# C.net
KiCad netlist of a schematic drawn in Altium Designer
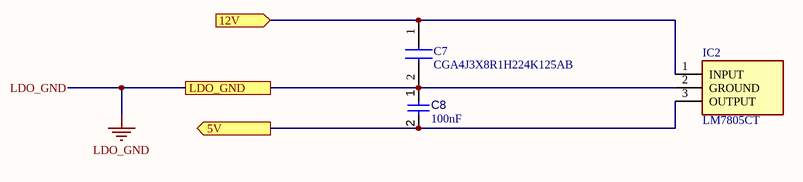
[diagram p0: C.SchDoc]

(export (version "E")
  (design (tool "Eeschema 10.0.6"))
  (components
    (comp (ref "C7")
      (value "CGA4J3X8R1H224K125AB")
      (footprint "SamacSys:CGA4J2NP01H223J125AA")
      (description "Capacitor")
      (fields (field (name "MOUSER PART NUMBER") "810-CGA4J3X8R1H224KB"))
      (libsource (lib "*") (part "CGA4J3X8R1H224K125AB"))
    )
    (comp (ref "C8")
      (value "100nF")
      (footprint "CAPC2013X95X50LL10T25")
      (description "Chip Capacitor, 100 nF, +/- 10%, 50 V, 0805 (2012 Metric)")
      (fields (field (name "TOLERANCE") "10%") (field (name "Comment") "Capacitor 100 nF +/-10% 50 V 0805"))
      (libsource (lib "Hector Dela Rosa") (part "CAP-NP-2"))
    )
    (comp (ref "IC2")
      (value "LM7805CT")
      (footprint "SamacSys:TO254P470X1028X1955-3P")
      (description "Integrated Circuit")
      (fields (field (name "MOUSER PART NUMBER") "926-LM7805CT"))
      (libsource (lib "*") (part "LM7805CT"))
    )
  )
  (nets
    (net (code "1") (name "/5V") (class "Default")
      (node (ref "C8") (pin "2") (pinfunction "2_2") (pintype "passive"))
      (node (ref "IC2") (pin "3") (pinfunction "OUTPUT_3") (pintype "passive"))
    )
    (net (code "2") (name "/12V") (class "Default")
      (node (ref "C7") (pin "1") (pinfunction "1_1") (pintype "passive"))
      (node (ref "IC2") (pin "1") (pinfunction "INPUT_1") (pintype "passive"))
    )
    (net (code "3") (name "LDO_GND") (class "Default")
      (node (ref "C7") (pin "2") (pinfunction "2_2") (pintype "passive"))
      (node (ref "C8") (pin "1") (pinfunction "1_1") (pintype "passive"))
      (node (ref "IC2") (pin "2") (pinfunction "GROUND_2") (pintype "passive"))
    )
  )
)
